# midicontroller.net
KiCad netlist of a schematic drawn in EAGLE
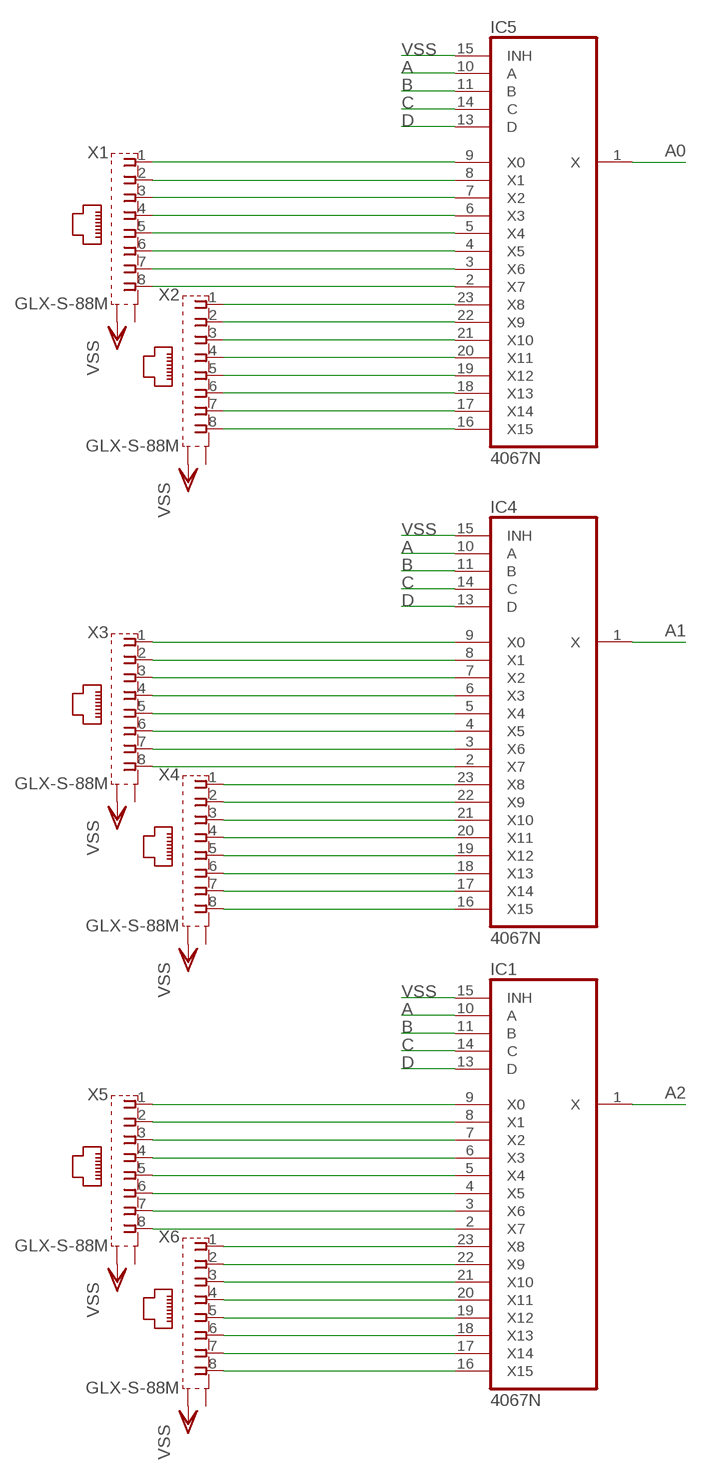
[diagram p0: schematic, sheet 1]

(export (version "E")
  (design (tool "Eeschema 10.0.6"))
  (components
    (comp (ref "IC1")
      (value "4067N")
      (footprint "eagle-import:DIL24-6")
      (libsource (lib "eagle-import") (part "4067N"))
    )
    (comp (ref "IC4")
      (value "4067N")
      (footprint "eagle-import:DIL24-6")
      (libsource (lib "eagle-import") (part "4067N"))
    )
    (comp (ref "IC5")
      (value "4067N")
      (footprint "eagle-import:DIL24-6")
      (libsource (lib "eagle-import") (part "4067N"))
    )
    (comp (ref "X1")
      (value "GLX-S-88M")
      (footprint "eagle-import:GLX-S-88M")
      (libsource (lib "eagle-import") (part "GLX-S-88M"))
    )
    (comp (ref "X2")
      (value "GLX-S-88M")
      (footprint "eagle-import:GLX-S-88M")
      (libsource (lib "eagle-import") (part "GLX-S-88M"))
    )
    (comp (ref "X3")
      (value "GLX-S-88M")
      (footprint "eagle-import:GLX-S-88M")
      (libsource (lib "eagle-import") (part "GLX-S-88M"))
    )
    (comp (ref "X4")
      (value "GLX-S-88M")
      (footprint "eagle-import:GLX-S-88M")
      (libsource (lib "eagle-import") (part "GLX-S-88M"))
    )
    (comp (ref "X5")
      (value "GLX-S-88M")
      (footprint "eagle-import:GLX-S-88M")
      (libsource (lib "eagle-import") (part "GLX-S-88M"))
    )
    (comp (ref "X6")
      (value "GLX-S-88M")
      (footprint "eagle-import:GLX-S-88M")
      (libsource (lib "eagle-import") (part "GLX-S-88M"))
    )
  )
  (nets
    (net (code "1") (name "/A") (class "Default")
      (node (ref "IC1") (pin "10") (pinfunction "A_10") (pintype "input"))
      (node (ref "IC4") (pin "10") (pinfunction "A_10") (pintype "input"))
      (node (ref "IC5") (pin "10") (pinfunction "A_10") (pintype "input"))
    )
    (net (code "2") (name "/A0") (class "Default")
      (node (ref "IC5") (pin "1") (pinfunction "X_1") (pintype "output"))
    )
    (net (code "3") (name "/A1") (class "Default")
      (node (ref "IC4") (pin "1") (pinfunction "X_1") (pintype "output"))
    )
    (net (code "4") (name "/A2") (class "Default")
      (node (ref "IC1") (pin "1") (pinfunction "X_1") (pintype "output"))
    )
    (net (code "5") (name "/B") (class "Default")
      (node (ref "IC1") (pin "11") (pinfunction "B_11") (pintype "input"))
      (node (ref "IC4") (pin "11") (pinfunction "B_11") (pintype "input"))
      (node (ref "IC5") (pin "11") (pinfunction "B_11") (pintype "input"))
    )
    (net (code "6") (name "/C") (class "Default")
      (node (ref "IC1") (pin "14") (pinfunction "C_14") (pintype "input"))
      (node (ref "IC4") (pin "14") (pinfunction "C_14") (pintype "input"))
      (node (ref "IC5") (pin "14") (pinfunction "C_14") (pintype "input"))
    )
    (net (code "7") (name "/D") (class "Default")
      (node (ref "IC1") (pin "13") (pinfunction "D_13") (pintype "input"))
      (node (ref "IC4") (pin "13") (pinfunction "D_13") (pintype "input"))
      (node (ref "IC5") (pin "13") (pinfunction "D_13") (pintype "input"))
    )
    (net (code "8") (name "Net-(IC1A-X0)") (class "Default")
      (node (ref "IC1") (pin "9") (pinfunction "X0_9") (pintype "input"))
      (node (ref "X5") (pin "1") (pinfunction "1_1") (pintype "passive"))
    )
    (net (code "9") (name "Net-(IC1A-X1)") (class "Default")
      (node (ref "IC1") (pin "8") (pinfunction "X1_8") (pintype "input"))
      (node (ref "X5") (pin "2") (pinfunction "2_2") (pintype "passive"))
    )
    (net (code "10") (name "Net-(IC1A-X2)") (class "Default")
      (node (ref "IC1") (pin "7") (pinfunction "X2_7") (pintype "input"))
      (node (ref "X5") (pin "3") (pinfunction "3_3") (pintype "passive"))
    )
    (net (code "11") (name "Net-(IC1A-X3)") (class "Default")
      (node (ref "IC1") (pin "6") (pinfunction "X3_6") (pintype "input"))
      (node (ref "X5") (pin "4") (pinfunction "4_4") (pintype "passive"))
    )
    (net (code "12") (name "Net-(IC1A-X4)") (class "Default")
      (node (ref "IC1") (pin "5") (pinfunction "X4_5") (pintype "input"))
      (node (ref "X5") (pin "5") (pinfunction "5_5") (pintype "passive"))
    )
    (net (code "13") (name "Net-(IC1A-X5)") (class "Default")
      (node (ref "IC1") (pin "4") (pinfunction "X5_4") (pintype "input"))
      (node (ref "X5") (pin "6") (pinfunction "6_6") (pintype "passive"))
    )
    (net (code "14") (name "Net-(IC1A-X6)") (class "Default")
      (node (ref "IC1") (pin "3") (pinfunction "X6_3") (pintype "input"))
      (node (ref "X5") (pin "7") (pinfunction "7_7") (pintype "passive"))
    )
    (net (code "15") (name "Net-(IC1A-X7)") (class "Default")
      (node (ref "IC1") (pin "2") (pinfunction "X7_2") (pintype "input"))
      (node (ref "X5") (pin "8") (pinfunction "8_8") (pintype "passive"))
    )
    (net (code "16") (name "Net-(IC1A-X8)") (class "Default")
      (node (ref "IC1") (pin "23") (pinfunction "X8_23") (pintype "input"))
      (node (ref "X6") (pin "1") (pinfunction "1_1") (pintype "passive"))
    )
    (net (code "17") (name "Net-(IC1A-X9)") (class "Default")
      (node (ref "IC1") (pin "22") (pinfunction "X9_22") (pintype "input"))
      (node (ref "X6") (pin "2") (pinfunction "2_2") (pintype "passive"))
    )
    (net (code "18") (name "Net-(IC1A-X10)") (class "Default")
      (node (ref "IC1") (pin "21") (pinfunction "X10_21") (pintype "input"))
      (node (ref "X6") (pin "3") (pinfunction "3_3") (pintype "passive"))
    )
    (net (code "19") (name "Net-(IC1A-X11)") (class "Default")
      (node (ref "IC1") (pin "20") (pinfunction "X11_20") (pintype "input"))
      (node (ref "X6") (pin "4") (pinfunction "4_4") (pintype "passive"))
    )
    (net (code "20") (name "Net-(IC1A-X12)") (class "Default")
      (node (ref "IC1") (pin "19") (pinfunction "X12_19") (pintype "input"))
      (node (ref "X6") (pin "5") (pinfunction "5_5") (pintype "passive"))
    )
    (net (code "21") (name "Net-(IC1A-X13)") (class "Default")
      (node (ref "IC1") (pin "18") (pinfunction "X13_18") (pintype "input"))
      (node (ref "X6") (pin "6") (pinfunction "6_6") (pintype "passive"))
    )
    (net (code "22") (name "Net-(IC1A-X14)") (class "Default")
      (node (ref "IC1") (pin "17") (pinfunction "X14_17") (pintype "input"))
      (node (ref "X6") (pin "7") (pinfunction "7_7") (pintype "passive"))
    )
    (net (code "23") (name "Net-(IC1A-X15)") (class "Default")
      (node (ref "IC1") (pin "16") (pinfunction "X15_16") (pintype "input"))
      (node (ref "X6") (pin "8") (pinfunction "8_8") (pintype "passive"))
    )
    (net (code "24") (name "Net-(IC4A-X0)") (class "Default")
      (node (ref "IC4") (pin "9") (pinfunction "X0_9") (pintype "input"))
      (node (ref "X3") (pin "1") (pinfunction "1_1") (pintype "passive"))
    )
    (net (code "25") (name "Net-(IC4A-X1)") (class "Default")
      (node (ref "IC4") (pin "8") (pinfunction "X1_8") (pintype "input"))
      (node (ref "X3") (pin "2") (pinfunction "2_2") (pintype "passive"))
    )
    (net (code "26") (name "Net-(IC4A-X2)") (class "Default")
      (node (ref "IC4") (pin "7") (pinfunction "X2_7") (pintype "input"))
      (node (ref "X3") (pin "3") (pinfunction "3_3") (pintype "passive"))
    )
    (net (code "27") (name "Net-(IC4A-X3)") (class "Default")
      (node (ref "IC4") (pin "6") (pinfunction "X3_6") (pintype "input"))
      (node (ref "X3") (pin "4") (pinfunction "4_4") (pintype "passive"))
    )
    (net (code "28") (name "Net-(IC4A-X4)") (class "Default")
      (node (ref "IC4") (pin "5") (pinfunction "X4_5") (pintype "input"))
      (node (ref "X3") (pin "5") (pinfunction "5_5") (pintype "passive"))
    )
    (net (code "29") (name "Net-(IC4A-X5)") (class "Default")
      (node (ref "IC4") (pin "4") (pinfunction "X5_4") (pintype "input"))
      (node (ref "X3") (pin "6") (pinfunction "6_6") (pintype "passive"))
    )
    (net (code "30") (name "Net-(IC4A-X6)") (class "Default")
      (node (ref "IC4") (pin "3") (pinfunction "X6_3") (pintype "input"))
      (node (ref "X3") (pin "7") (pinfunction "7_7") (pintype "passive"))
    )
    (net (code "31") (name "Net-(IC4A-X7)") (class "Default")
      (node (ref "IC4") (pin "2") (pinfunction "X7_2") (pintype "input"))
      (node (ref "X3") (pin "8") (pinfunction "8_8") (pintype "passive"))
    )
    (net (code "32") (name "Net-(IC4A-X8)") (class "Default")
      (node (ref "IC4") (pin "23") (pinfunction "X8_23") (pintype "input"))
      (node (ref "X4") (pin "1") (pinfunction "1_1") (pintype "passive"))
    )
    (net (code "33") (name "Net-(IC4A-X9)") (class "Default")
      (node (ref "IC4") (pin "22") (pinfunction "X9_22") (pintype "input"))
      (node (ref "X4") (pin "2") (pinfunction "2_2") (pintype "passive"))
    )
    (net (code "34") (name "Net-(IC4A-X10)") (class "Default")
      (node (ref "IC4") (pin "21") (pinfunction "X10_21") (pintype "input"))
      (node (ref "X4") (pin "3") (pinfunction "3_3") (pintype "passive"))
    )
    (net (code "35") (name "Net-(IC4A-X11)") (class "Default")
      (node (ref "IC4") (pin "20") (pinfunction "X11_20") (pintype "input"))
      (node (ref "X4") (pin "4") (pinfunction "4_4") (pintype "passive"))
    )
    (net (code "36") (name "Net-(IC4A-X12)") (class "Default")
      (node (ref "IC4") (pin "19") (pinfunction "X12_19") (pintype "input"))
      (node (ref "X4") (pin "5") (pinfunction "5_5") (pintype "passive"))
    )
    (net (code "37") (name "Net-(IC4A-X13)") (class "Default")
      (node (ref "IC4") (pin "18") (pinfunction "X13_18") (pintype "input"))
      (node (ref "X4") (pin "6") (pinfunction "6_6") (pintype "passive"))
    )
    (net (code "38") (name "Net-(IC4A-X14)") (class "Default")
      (node (ref "IC4") (pin "17") (pinfunction "X14_17") (pintype "input"))
      (node (ref "X4") (pin "7") (pinfunction "7_7") (pintype "passive"))
    )
    (net (code "39") (name "Net-(IC4A-X15)") (class "Default")
      (node (ref "IC4") (pin "16") (pinfunction "X15_16") (pintype "input"))
      (node (ref "X4") (pin "8") (pinfunction "8_8") (pintype "passive"))
    )
    (net (code "40") (name "Net-(IC5A-X0)") (class "Default")
      (node (ref "IC5") (pin "9") (pinfunction "X0_9") (pintype "input"))
      (node (ref "X1") (pin "1") (pinfunction "1_1") (pintype "passive"))
    )
    (net (code "41") (name "Net-(IC5A-X1)") (class "Default")
      (node (ref "IC5") (pin "8") (pinfunction "X1_8") (pintype "input"))
      (node (ref "X1") (pin "2") (pinfunction "2_2") (pintype "passive"))
    )
    (net (code "42") (name "Net-(IC5A-X2)") (class "Default")
      (node (ref "IC5") (pin "7") (pinfunction "X2_7") (pintype "input"))
      (node (ref "X1") (pin "3") (pinfunction "3_3") (pintype "passive"))
    )
    (net (code "43") (name "Net-(IC5A-X3)") (class "Default")
      (node (ref "IC5") (pin "6") (pinfunction "X3_6") (pintype "input"))
      (node (ref "X1") (pin "4") (pinfunction "4_4") (pintype "passive"))
    )
    (net (code "44") (name "Net-(IC5A-X4)") (class "Default")
      (node (ref "IC5") (pin "5") (pinfunction "X4_5") (pintype "input"))
      (node (ref "X1") (pin "5") (pinfunction "5_5") (pintype "passive"))
    )
    (net (code "45") (name "Net-(IC5A-X5)") (class "Default")
      (node (ref "IC5") (pin "4") (pinfunction "X5_4") (pintype "input"))
      (node (ref "X1") (pin "6") (pinfunction "6_6") (pintype "passive"))
    )
    (net (code "46") (name "Net-(IC5A-X6)") (class "Default")
      (node (ref "IC5") (pin "3") (pinfunction "X6_3") (pintype "input"))
      (node (ref "X1") (pin "7") (pinfunction "7_7") (pintype "passive"))
    )
    (net (code "47") (name "Net-(IC5A-X7)") (class "Default")
      (node (ref "IC5") (pin "2") (pinfunction "X7_2") (pintype "input"))
      (node (ref "X1") (pin "8") (pinfunction "8_8") (pintype "passive"))
    )
    (net (code "48") (name "Net-(IC5A-X8)") (class "Default")
      (node (ref "IC5") (pin "23") (pinfunction "X8_23") (pintype "input"))
      (node (ref "X2") (pin "1") (pinfunction "1_1") (pintype "passive"))
    )
    (net (code "49") (name "Net-(IC5A-X9)") (class "Default")
      (node (ref "IC5") (pin "22") (pinfunction "X9_22") (pintype "input"))
      (node (ref "X2") (pin "2") (pinfunction "2_2") (pintype "passive"))
    )
    (net (code "50") (name "Net-(IC5A-X10)") (class "Default")
      (node (ref "IC5") (pin "21") (pinfunction "X10_21") (pintype "input"))
      (node (ref "X2") (pin "3") (pinfunction "3_3") (pintype "passive"))
    )
    (net (code "51") (name "Net-(IC5A-X11)") (class "Default")
      (node (ref "IC5") (pin "20") (pinfunction "X11_20") (pintype "input"))
      (node (ref "X2") (pin "4") (pinfunction "4_4") (pintype "passive"))
    )
    (net (code "52") (name "Net-(IC5A-X12)") (class "Default")
      (node (ref "IC5") (pin "19") (pinfunction "X12_19") (pintype "input"))
      (node (ref "X2") (pin "5") (pinfunction "5_5") (pintype "passive"))
    )
    (net (code "53") (name "Net-(IC5A-X13)") (class "Default")
      (node (ref "IC5") (pin "18") (pinfunction "X13_18") (pintype "input"))
      (node (ref "X2") (pin "6") (pinfunction "6_6") (pintype "passive"))
    )
    (net (code "54") (name "Net-(IC5A-X14)") (class "Default")
      (node (ref "IC5") (pin "17") (pinfunction "X14_17") (pintype "input"))
      (node (ref "X2") (pin "7") (pinfunction "7_7") (pintype "passive"))
    )
    (net (code "55") (name "Net-(IC5A-X15)") (class "Default")
      (node (ref "IC5") (pin "16") (pinfunction "X15_16") (pintype "input"))
      (node (ref "X2") (pin "8") (pinfunction "8_8") (pintype "passive"))
    )
    (net (code "56") (name "VSS") (class "Default")
      (node (ref "IC1") (pin "15") (pinfunction "INH_15") (pintype "input"))
      (node (ref "IC4") (pin "15") (pinfunction "INH_15") (pintype "input"))
      (node (ref "IC5") (pin "15") (pinfunction "INH_15") (pintype "input"))
      (node (ref "X1") (pin "S2") (pinfunction "S2_S2") (pintype "passive"))
      (node (ref "X2") (pin "S2") (pinfunction "S2_S2") (pintype "passive"))
      (node (ref "X3") (pin "S2") (pinfunction "S2_S2") (pintype "passive"))
      (node (ref "X4") (pin "S2") (pinfunction "S2_S2") (pintype "passive"))
      (node (ref "X5") (pin "S2") (pinfunction "S2_S2") (pintype "passive"))
      (node (ref "X6") (pin "S2") (pinfunction "S2_S2") (pintype "passive"))
    )
    (net (code "57") (name "unconnected-(X1-PadS1)") (class "Default")
      (node (ref "X1") (pin "S1") (pinfunction "S1_S1") (pintype "passive"))
    )
    (net (code "58") (name "unconnected-(X2-PadS1)") (class "Default")
      (node (ref "X2") (pin "S1") (pinfunction "S1_S1") (pintype "passive"))
    )
    (net (code "59") (name "unconnected-(X3-PadS1)") (class "Default")
      (node (ref "X3") (pin "S1") (pinfunction "S1_S1") (pintype "passive"))
    )
    (net (code "60") (name "unconnected-(X4-PadS1)") (class "Default")
      (node (ref "X4") (pin "S1") (pinfunction "S1_S1") (pintype "passive"))
    )
    (net (code "61") (name "unconnected-(X5-PadS1)") (class "Default")
      (node (ref "X5") (pin "S1") (pinfunction "S1_S1") (pintype "passive"))
    )
    (net (code "62") (name "unconnected-(X6-PadS1)") (class "Default")
      (node (ref "X6") (pin "S1") (pinfunction "S1_S1") (pintype "passive"))
    )
  )
)
